# led-drv.net
KiCad netlist of a schematic drawn in EAGLE
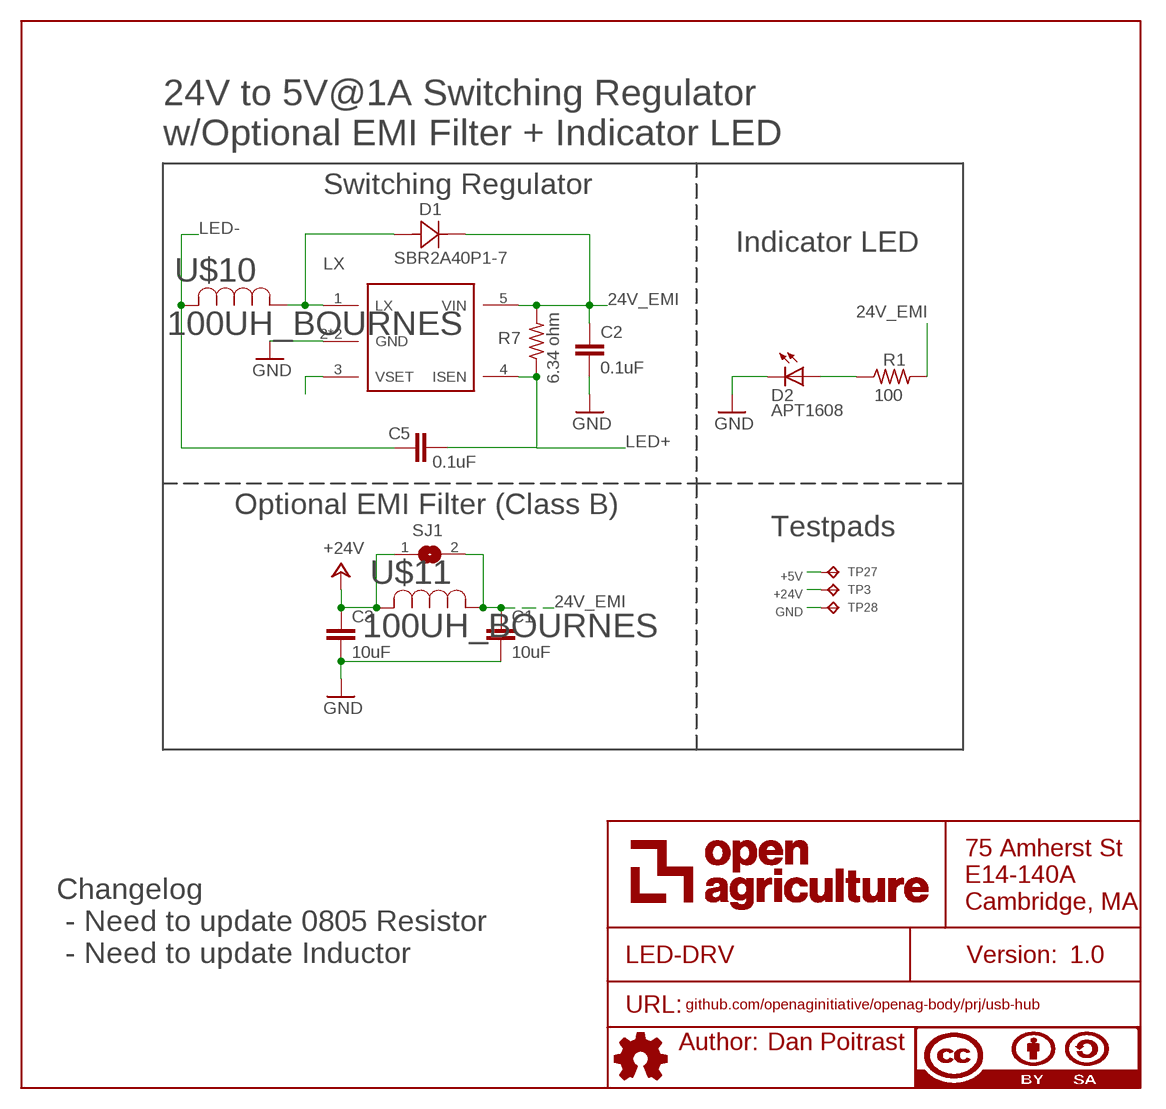
[diagram p0: schematic, sheet 1]

(export (version "E")
  (design (tool "Eeschema 10.0.6"))
  (components
    (comp (ref "C1")
      (value "10uF")
      (footprint "eagle-import:C0805")
      (fields (field (name "MANUFACTURER") "Taiyo Yuden") (field (name "MPN") "GMK212BBJ106KG-T"))
      (libsource (lib "eagle-import") (part "10UF-GMK212BBJ106KG-T"))
    )
    (comp (ref "C2")
      (value "0.1uF")
      (footprint "eagle-import:C0603")
      (fields (field (name "MANUFACTURER") "Kemet") (field (name "MPN") "C0603C104K5RACTU"))
      (libsource (lib "eagle-import") (part "0.1UF-C0603C104K5RACTU"))
    )
    (comp (ref "C3")
      (value "10uF")
      (footprint "eagle-import:C0805")
      (fields (field (name "MANUFACTURER") "Taiyo Yuden") (field (name "MPN") "GMK212BBJ106KG-T"))
      (libsource (lib "eagle-import") (part "10UF-GMK212BBJ106KG-T"))
    )
    (comp (ref "C5")
      (value "0.1uF")
      (footprint "eagle-import:C0603")
      (fields (field (name "MANUFACTURER") "Kemet") (field (name "MPN") "C0603C104K5RACTU"))
      (libsource (lib "eagle-import") (part "0.1UF-C0603C104K5RACTU"))
    )
    (comp (ref "D1")
      (value "SBR2A40P1-7")
      (footprint "eagle-import:POWERDI123")
      (fields (field (name "MANUFACTURER") "Diodes Incorporated"))
      (libsource (lib "eagle-import") (part "SBR2A40P1-7"))
    )
    (comp (ref "D2")
      (value "APT1608")
      (footprint "eagle-import:CHIPLED_0603")
      (fields (field (name "MANUFACTURER") "Kingbright") (field (name "MPN") "APT1608CGCK"))
      (libsource (lib "eagle-import") (part "APT1608CGCK"))
    )
    (comp (ref "R1")
      (value "100")
      (footprint "eagle-import:RC0603N")
      (fields (field (name "MANUFACTURER") "Yageo") (field (name "MPN") "RC0603JR-07100RL"))
      (libsource (lib "eagle-import") (part "100OHM-RC0603JR-07100RL"))
    )
    (comp (ref "R7")
      (value "6.34 ohm")
      (footprint "eagle-import:R0805")
      (libsource (lib "eagle-import") (part "6.3OHM-RC0805FR-076R34L"))
    )
    (comp (ref "SJ1")
      (value "SOLDERJUMPERREFLOW_NOPASTE")
      (footprint "eagle-import:SJ1")
      (libsource (lib "eagle-import") (part "SOLDERJUMPERREFLOW_NOPASTE"))
    )
    (comp (ref "TP3")
      (value "TPTP06R")
      (footprint "eagle-import:TP06R")
      (libsource (lib "eagle-import") (part "TPTP06R"))
    )
    (comp (ref "TP27")
      (value "TPTP06R")
      (footprint "eagle-import:TP06R")
      (libsource (lib "eagle-import") (part "TPTP06R"))
    )
    (comp (ref "TP28")
      (value "TPTP06R")
      (footprint "eagle-import:TP06R")
      (libsource (lib "eagle-import") (part "TPTP06R"))
    )
    (comp (ref "U$6")
      (value "AUTHOR")
      (footprint "eagle-import:AUTHOR")
      (fields (field (name "AUTHOR") "Dan Poitrast"))
      (libsource (lib "eagle-import") (part "AUTHOR"))
    )
    (comp (ref "U$7")
      (value "TITLE")
      (footprint "eagle-import:TITLE")
      (fields
        (field (name "TITLE") "LED-DRV")
        (field (name "URL") "github.com/openaginitiative/openag-body/prj/usb-hub")
      )
      (libsource (lib "eagle-import") (part "TITLE"))
    )
    (comp (ref "U$9")
      (value "AL8861")
      (footprint "eagle-import:AL8861")
      (libsource (lib "eagle-import") (part "AL8861"))
    )
    (comp (ref "U$10")
      (value "100UH_BOURNES")
      (footprint "eagle-import:IND_BOURNS_SDR1307")
      (libsource (lib "eagle-import") (part "100UH_BOURNES"))
    )
    (comp (ref "U$11")
      (value "100UH_BOURNES")
      (footprint "eagle-import:IND_BOURNS_SDR1307")
      (libsource (lib "eagle-import") (part "100UH_BOURNES"))
    )
  )
  (nets
    (net (code "1") (name "+5V") (class "Default")
      (node (ref "TP27") (pin "TP") (pinfunction "TP_TP") (pintype "input"))
    )
    (net (code "2") (name "+24V") (class "Default")
      (node (ref "C3") (pin "1") (pinfunction "1_1") (pintype "passive"))
      (node (ref "SJ1") (pin "1") (pinfunction "1_1") (pintype "passive"))
      (node (ref "TP3") (pin "TP") (pinfunction "TP_TP") (pintype "input"))
      (node (ref "U$11") (pin "2") (pinfunction "2_2") (pintype "passive"))
    )
    (net (code "3") (name "/LX") (class "Default")
      (node (ref "D1") (pin "+") (pinfunction "+_+") (pintype "passive"))
      (node (ref "U$10") (pin "1") (pinfunction "1_1") (pintype "passive"))
      (node (ref "U$9") (pin "1") (pinfunction "LX_1") (pintype "bidirectional"))
    )
    (net (code "4") (name "24V_EMI") (class "Default")
      (node (ref "C1") (pin "1") (pinfunction "1_1") (pintype "passive"))
      (node (ref "C2") (pin "1") (pinfunction "1_1") (pintype "passive"))
      (node (ref "D1") (pin "-") (pinfunction "-_-") (pintype "passive"))
      (node (ref "R1") (pin "2") (pinfunction "2_2") (pintype "passive"))
      (node (ref "R7") (pin "2") (pinfunction "2_2") (pintype "passive"))
      (node (ref "SJ1") (pin "2") (pinfunction "2_2") (pintype "passive"))
      (node (ref "U$11") (pin "1") (pinfunction "1_1") (pintype "passive"))
      (node (ref "U$9") (pin "5") (pinfunction "VIN_5") (pintype "bidirectional"))
    )
    (net (code "5") (name "GND") (class "Default")
      (node (ref "C1") (pin "2") (pinfunction "2_2") (pintype "passive"))
      (node (ref "C2") (pin "2") (pinfunction "2_2") (pintype "passive"))
      (node (ref "C3") (pin "2") (pinfunction "2_2") (pintype "passive"))
      (node (ref "D2") (pin "C") (pinfunction "C_C") (pintype "passive"))
      (node (ref "TP28") (pin "TP") (pinfunction "TP_TP") (pintype "input"))
      (node (ref "U$9") (pin "2") (pinfunction "GND_2") (pintype "bidirectional"))
      (node (ref "U$9") (pin "44") (pinfunction "GND_44") (pintype "bidirectional"))
    )
    (net (code "6") (name "LED+") (class "Default")
      (node (ref "C5") (pin "2") (pinfunction "2_2") (pintype "passive"))
      (node (ref "R7") (pin "1") (pinfunction "1_1") (pintype "passive"))
      (node (ref "U$9") (pin "4") (pinfunction "ISEN_4") (pintype "bidirectional"))
    )
    (net (code "7") (name "LED-") (class "Default")
      (node (ref "C5") (pin "1") (pinfunction "1_1") (pintype "passive"))
      (node (ref "U$10") (pin "2") (pinfunction "2_2") (pintype "passive"))
    )
    (net (code "8") (name "Net-(D2-PadA)") (class "Default")
      (node (ref "D2") (pin "A") (pinfunction "A_A") (pintype "passive"))
      (node (ref "R1") (pin "1") (pinfunction "1_1") (pintype "passive"))
    )
    (net (code "9") (name "unconnected-(U$9-VSET-Pad3)") (class "Default")
      (node (ref "U$9") (pin "3") (pinfunction "VSET_3") (pintype "bidirectional"))
    )
  )
)
